# MT2492_Schem.net
KiCad netlist of a schematic drawn in Altium Designer
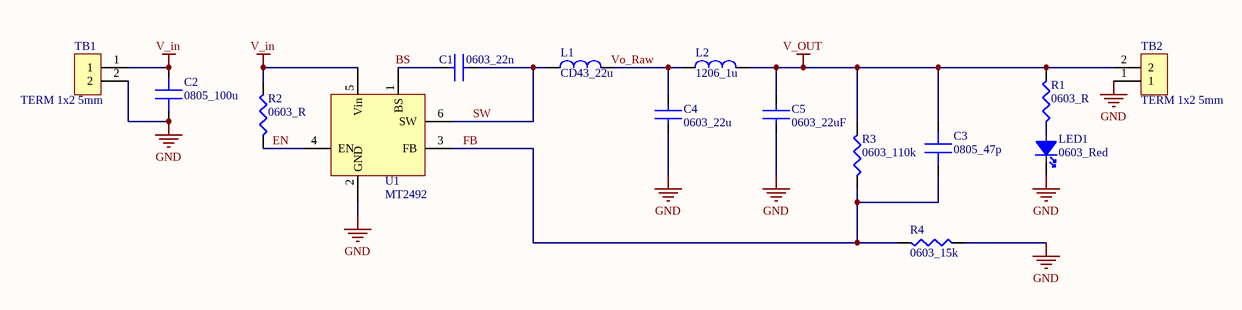
[diagram p0: MT2492_Schem.SchDoc]

(export (version "E")
  (design (tool "Eeschema 10.0.6"))
  (components
    (comp (ref "C1")
      (value "0603_22n")
      (footprint "0603_CAP")
      (libsource (lib "TimerSMD_Components") (part "0603 Capacitor"))
    )
    (comp (ref "C2")
      (value "0805_100u")
      (footprint "C0805 - 0.1uf")
      (description "0805 Capacitor")
      (libsource (lib "TimerSMD_Components") (part "0805 Capacitor"))
    )
    (comp (ref "C3")
      (value "0805_47p")
      (footprint "C0805 - 0.1uf")
      (description "0805 Capacitor")
      (libsource (lib "TimerSMD_Components") (part "0805 Capacitor"))
    )
    (comp (ref "C4")
      (value "0603_22u")
      (footprint "0603_CAP")
      (libsource (lib "TimerSMD_Components") (part "0603 Capacitor"))
    )
    (comp (ref "C5")
      (value "0603_22uF")
      (footprint "0603_CAP")
      (libsource (lib "TimerSMD_Components") (part "0603 Capacitor"))
    )
    (comp (ref "L1")
      (value "CD43_22u")
      (footprint "CD43")
      (description "Inductor RF Chip Shielded Multi-Layer 10uH 10% 2MHz 45Q-Factor 0.025A 1Ohm DCR 1206 T/R")
      (fields (field (name "TOLERANCE") "10%"))
      (libsource (lib "TimerSMD_Components") (part "ILSB1206ER100K"))
    )
    (comp (ref "L2")
      (value "1206_1u")
      (footprint "1206")
      (description "Inductor RF Chip Shielded Multi-Layer 10uH 10% 2MHz 45Q-Factor 0.025A 1Ohm DCR 1206 T/R")
      (fields (field (name "TOLERANCE") "10%"))
      (libsource (lib "TimerSMD_Components") (part "ILSB1206ER100K"))
    )
    (comp (ref "LED1")
      (value "0603_Red")
      (footprint "0603_LED")
      (libsource (lib "TimerSMD_Components") (part "0603LED"))
    )
    (comp (ref "R1")
      (value "0603_R")
      (footprint "0603_CAP")
      (libsource (lib "TimerSMD_Components") (part "0603 Resistor"))
    )
    (comp (ref "R2")
      (value "0603_R")
      (footprint "0603_CAP")
      (libsource (lib "TimerSMD_Components") (part "0603 Resistor"))
    )
    (comp (ref "R3")
      (value "0603_110k")
      (footprint "0603_CAP")
      (libsource (lib "TimerSMD_Components") (part "0603 Resistor"))
    )
    (comp (ref "R4")
      (value "0603_15k")
      (footprint "0603_CAP")
      (libsource (lib "TimerSMD_Components") (part "0603 Resistor"))
    )
    (comp (ref "TB1")
      (value "TERM 1x2 5mm")
      (footprint "Terminal_5mm")
      (fields (field (name "VOLTAGE") "300V"))
      (libsource (lib "TimerSMD_Components") (part "Terminal BLK Green"))
    )
    (comp (ref "TB2")
      (value "TERM 1x2 5mm")
      (footprint "Terminal_5mm")
      (fields (field (name "VOLTAGE") "300V"))
      (libsource (lib "") (part "Terminal BLK Green_1"))
    )
    (comp (ref "U1")
      (value "MT2492")
      (footprint "SOT23-6")
      (description "2A Buck Converter")
      (libsource (lib "TimerSMD_Components") (part "MT2492"))
    )
  )
  (nets
    (net (code "1") (name "/BS") (class "Default")
      (node (ref "C1") (pin "1") (pinfunction "1_1") (pintype "passive"))
      (node (ref "U1") (pin "1") (pinfunction "BS_1") (pintype "passive"))
    )
    (net (code "2") (name "/EN") (class "Default")
      (node (ref "R2") (pin "1") (pinfunction "1_1") (pintype "passive"))
      (node (ref "U1") (pin "4") (pinfunction "EN_4") (pintype "passive"))
    )
    (net (code "3") (name "/FB") (class "Default")
      (node (ref "C3") (pin "1") (pinfunction "1_1") (pintype "passive"))
      (node (ref "R3") (pin "1") (pinfunction "1_1") (pintype "passive"))
      (node (ref "R4") (pin "2") (pinfunction "2_2") (pintype "passive"))
      (node (ref "U1") (pin "3") (pinfunction "FB_3") (pintype "passive"))
    )
    (net (code "4") (name "/SW") (class "Default")
      (node (ref "C1") (pin "2") (pinfunction "2_2") (pintype "passive"))
      (node (ref "L1") (pin "1") (pinfunction "1_1") (pintype "passive"))
      (node (ref "U1") (pin "6") (pinfunction "SW_6") (pintype "passive"))
    )
    (net (code "5") (name "/Vo_Raw") (class "Default")
      (node (ref "C4") (pin "2") (pinfunction "2_2") (pintype "passive"))
      (node (ref "L1") (pin "2") (pinfunction "2_2") (pintype "passive"))
      (node (ref "L2") (pin "1") (pinfunction "1_1") (pintype "passive"))
    )
    (net (code "6") (name "GND") (class "Default")
      (node (ref "C2") (pin "1") (pinfunction "1_1") (pintype "passive"))
      (node (ref "C4") (pin "1") (pinfunction "1_1") (pintype "passive"))
      (node (ref "C5") (pin "1") (pinfunction "1_1") (pintype "passive"))
      (node (ref "LED1") (pin "2") (pinfunction "Cathode_2") (pintype "passive"))
      (node (ref "R4") (pin "1") (pinfunction "1_1") (pintype "passive"))
      (node (ref "TB1") (pin "2") (pinfunction "2_2") (pintype "passive"))
      (node (ref "TB2") (pin "1") (pinfunction "1_1") (pintype "passive"))
      (node (ref "U1") (pin "2") (pinfunction "GND_2") (pintype "passive"))
    )
    (net (code "7") (name "Net-(LED1-Anode)") (class "Default")
      (node (ref "LED1") (pin "1") (pinfunction "Anode_1") (pintype "passive"))
      (node (ref "R1") (pin "1") (pinfunction "1_1") (pintype "passive"))
    )
    (net (code "8") (name "V_OUT") (class "Default")
      (node (ref "C3") (pin "2") (pinfunction "2_2") (pintype "passive"))
      (node (ref "C5") (pin "2") (pinfunction "2_2") (pintype "passive"))
      (node (ref "L2") (pin "2") (pinfunction "2_2") (pintype "passive"))
      (node (ref "R1") (pin "2") (pinfunction "2_2") (pintype "passive"))
      (node (ref "R3") (pin "2") (pinfunction "2_2") (pintype "passive"))
      (node (ref "TB2") (pin "2") (pinfunction "2_2") (pintype "passive"))
    )
    (net (code "9") (name "V_in") (class "Default")
      (node (ref "C2") (pin "2") (pinfunction "2_2") (pintype "passive"))
      (node (ref "R2") (pin "2") (pinfunction "2_2") (pintype "passive"))
      (node (ref "TB1") (pin "1") (pinfunction "1_1") (pintype "passive"))
      (node (ref "U1") (pin "5") (pinfunction "Vin_5") (pintype "passive"))
    )
  )
)
